# lightmeter_seeed1.net
KiCad netlist of a schematic drawn in EAGLE
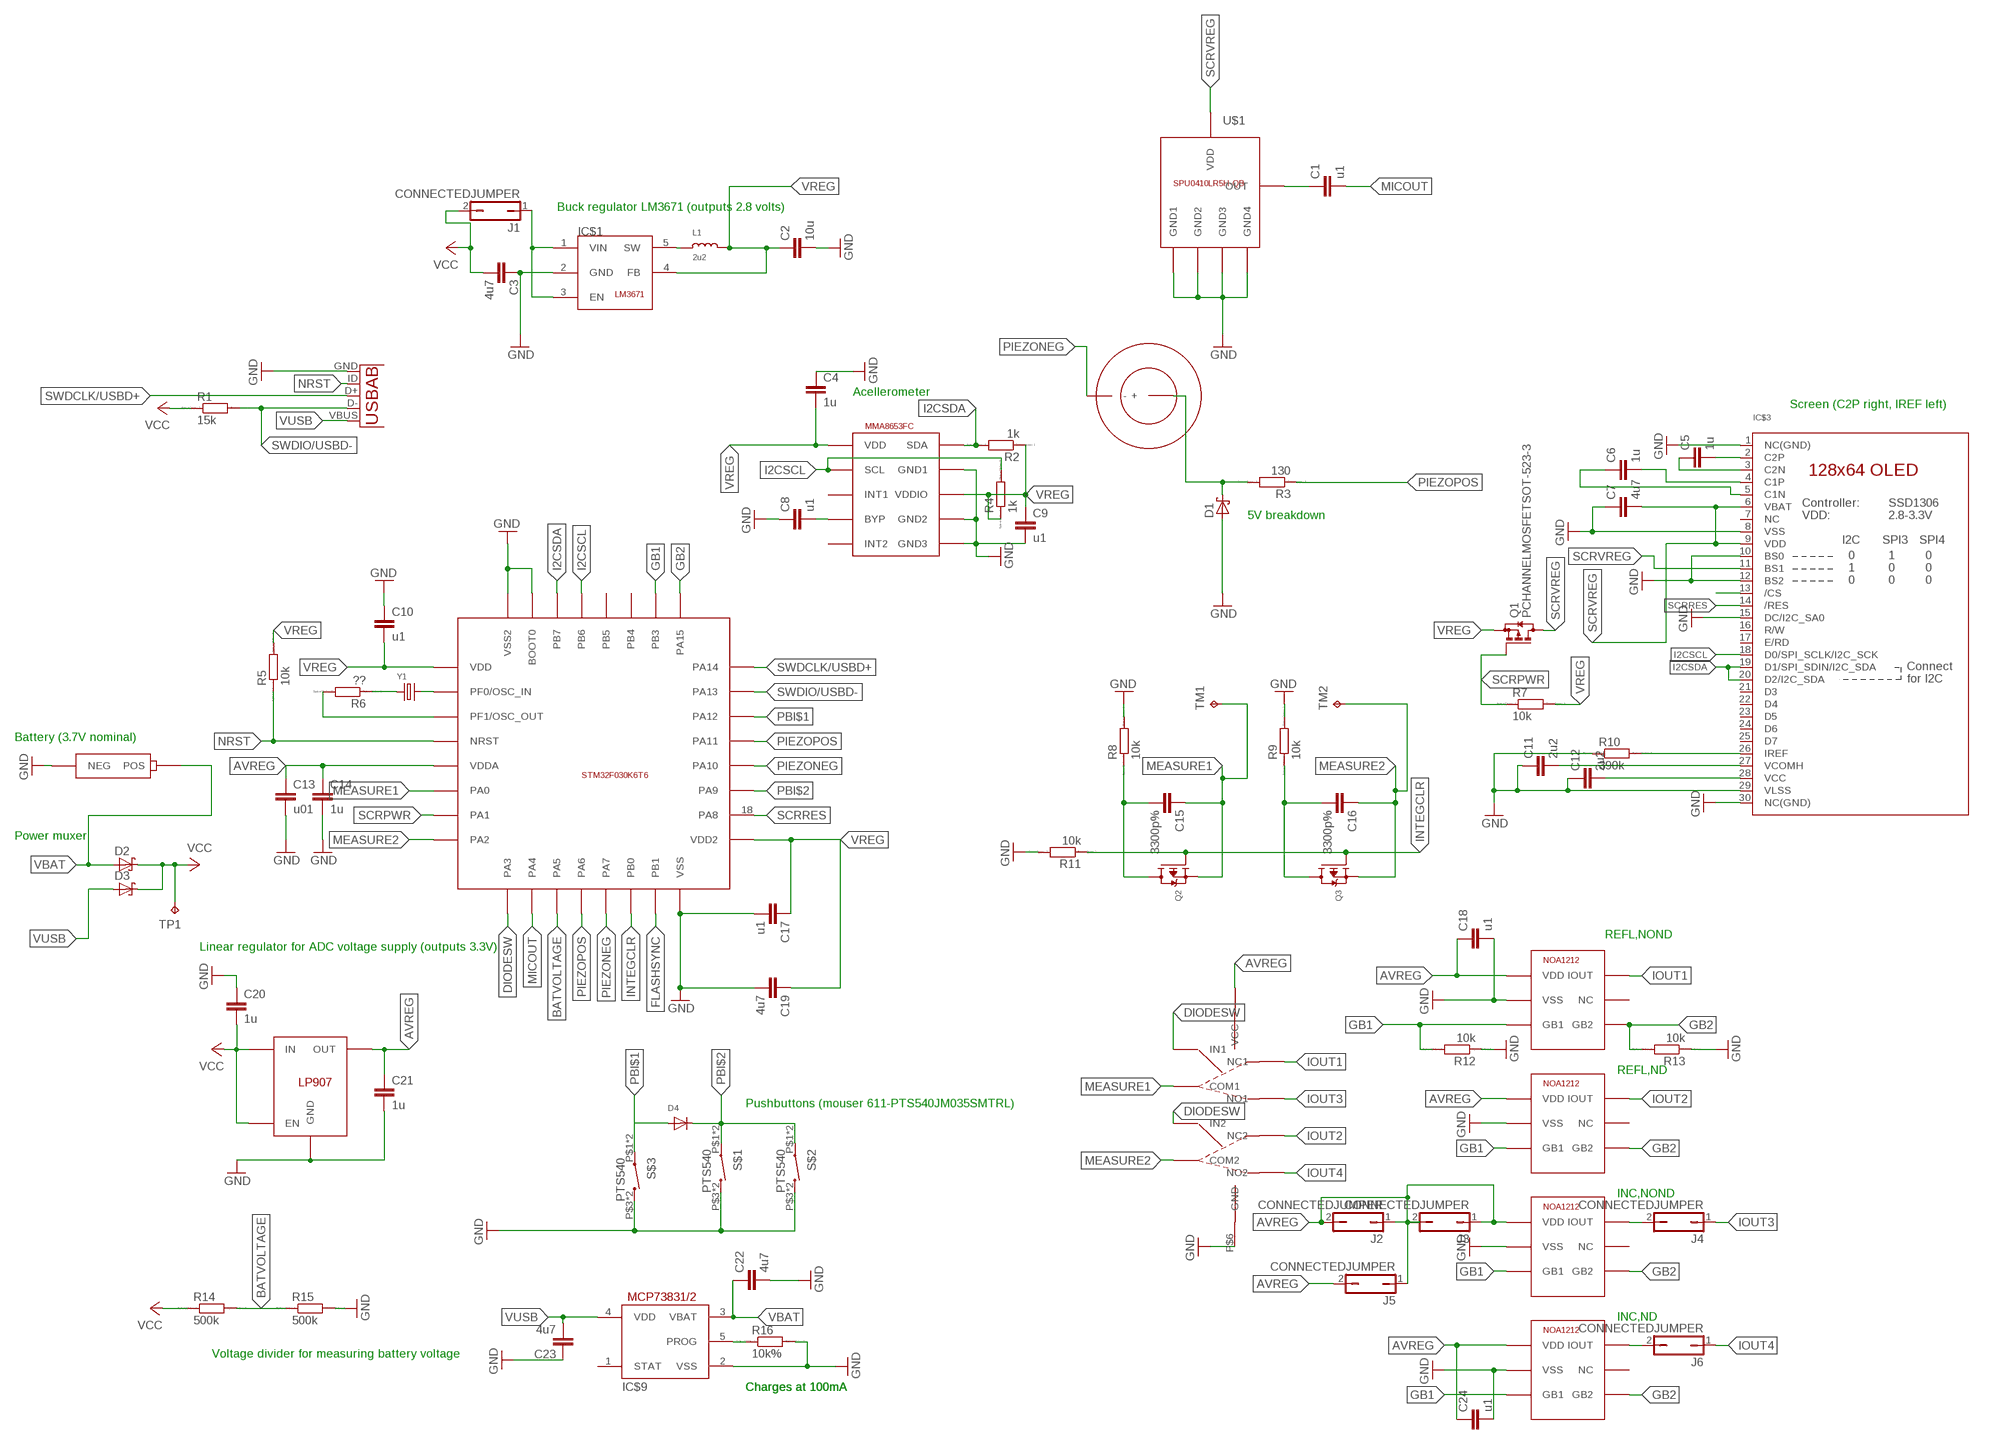
[diagram p0: schematic, sheet 1]

(export (version "E")
  (design (tool "Eeschema 10.0.6"))
  (components
    (comp (ref "C1")
      (value "u1")
      (footprint "eagle-import:C0402")
      (libsource (lib "eagle-import") (part "C-EUC0402"))
    )
    (comp (ref "C2")
      (value "10u")
      (footprint "eagle-import:C0402")
      (libsource (lib "eagle-import") (part "C-EUC0402"))
    )
    (comp (ref "C3")
      (value "4u7")
      (footprint "eagle-import:C0402")
      (libsource (lib "eagle-import") (part "C-EUC0402"))
    )
    (comp (ref "C4")
      (value "1u")
      (footprint "eagle-import:C0603")
      (libsource (lib "eagle-import") (part "C-EUC0603"))
    )
    (comp (ref "C5")
      (value "1u")
      (footprint "eagle-import:C0603")
      (libsource (lib "eagle-import") (part "C-EUC0603"))
    )
    (comp (ref "C6")
      (value "1u")
      (footprint "eagle-import:C0603")
      (libsource (lib "eagle-import") (part "C-EUC0603"))
    )
    (comp (ref "C7")
      (value "4u7")
      (footprint "eagle-import:C0402")
      (libsource (lib "eagle-import") (part "C-EUC0402"))
    )
    (comp (ref "C8")
      (value "u1")
      (footprint "eagle-import:C0603")
      (libsource (lib "eagle-import") (part "C-EUC0603"))
    )
    (comp (ref "C9")
      (value "u1")
      (footprint "eagle-import:C0402")
      (libsource (lib "eagle-import") (part "C-EUC0402"))
    )
    (comp (ref "C10")
      (value "u1")
      (footprint "eagle-import:C0402")
      (libsource (lib "eagle-import") (part "C-EUC0402"))
    )
    (comp (ref "C11")
      (value "2u2")
      (footprint "eagle-import:C0402")
      (libsource (lib "eagle-import") (part "C-EUC0402"))
    )
    (comp (ref "C12")
      (value "2u2")
      (footprint "eagle-import:C0402")
      (libsource (lib "eagle-import") (part "C-EUC0402"))
    )
    (comp (ref "C13")
      (value "u01")
      (footprint "eagle-import:GAP0402")
      (libsource (lib "eagle-import") (part "CGAP0402"))
    )
    (comp (ref "C14")
      (value "1u")
      (footprint "eagle-import:GAP0402")
      (libsource (lib "eagle-import") (part "CGAP0402"))
    )
    (comp (ref "C15")
      (value "3300p%")
      (footprint "eagle-import:C0603")
      (libsource (lib "eagle-import") (part "C-EUC0603"))
    )
    (comp (ref "C16")
      (value "3300p%")
      (footprint "eagle-import:C0603")
      (libsource (lib "eagle-import") (part "C-EUC0603"))
    )
    (comp (ref "C17")
      (value "u1")
      (footprint "eagle-import:C0402")
      (libsource (lib "eagle-import") (part "C-EUC0402"))
    )
    (comp (ref "C18")
      (value "u1")
      (footprint "eagle-import:C0402")
      (libsource (lib "eagle-import") (part "C-EUC0402"))
    )
    (comp (ref "C19")
      (value "4u7")
      (footprint "eagle-import:C0402")
      (libsource (lib "eagle-import") (part "C-EUC0402"))
    )
    (comp (ref "C20")
      (value "1u")
      (footprint "eagle-import:C0603")
      (libsource (lib "eagle-import") (part "C-EUC0603"))
    )
    (comp (ref "C21")
      (value "1u")
      (footprint "eagle-import:C0402")
      (libsource (lib "eagle-import") (part "C-EUC0402"))
    )
    (comp (ref "C22")
      (value "4u7")
      (footprint "eagle-import:C0402")
      (libsource (lib "eagle-import") (part "C-EUC0402"))
    )
    (comp (ref "C23")
      (value "4u7")
      (footprint "eagle-import:C0402")
      (libsource (lib "eagle-import") (part "C-EUC0402"))
    )
    (comp (ref "C24")
      (value "u1")
      (footprint "eagle-import:C0402")
      (libsource (lib "eagle-import") (part "C-EUC0402"))
    )
    (comp (ref "D1")
      (value "SCHOTTKY-DIODESOD-929")
      (footprint "eagle-import:SOD-923")
      (libsource (lib "eagle-import") (part "SCHOTTKY-DIODESOD-929"))
    )
    (comp (ref "D2")
      (value "SCHOTTKY-DIODEX3-DFN0603-2")
      (footprint "eagle-import:X3-DFN0603-2")
      (libsource (lib "eagle-import") (part "SCHOTTKY-DIODEX3-DFN0603-2"))
    )
    (comp (ref "D3")
      (value "SCHOTTKY-DIODEX3-DFN0603-2")
      (footprint "eagle-import:X3-DFN0603-2")
      (libsource (lib "eagle-import") (part "SCHOTTKY-DIODEX3-DFN0603-2"))
    )
    (comp (ref "D4")
      (value "DIODESOD-323F")
      (footprint "eagle-import:SOD-323F")
      (libsource (lib "eagle-import") (part "DIODESOD-323F"))
    )
    (comp (ref "IC$1")
      (value "LM3671")
      (footprint "eagle-import:SOT23-5")
      (libsource (lib "eagle-import") (part "LM3671"))
    )
    (comp (ref "IC$2")
      (value "MMA8653")
      (footprint "eagle-import:DFN-10")
      (libsource (lib "eagle-import") (part "MMA8653"))
    )
    (comp (ref "IC$3")
      (value "DISP_OLED_UG-2864HSWEG010.96\"")
      (footprint "eagle-import:UG-2864HSWEG01_0.96IN_WRAPAROUND")
      (libsource (lib "eagle-import") (part "DISP_OLED_UG-2864HSWEG010.96{dblquote}"))
    )
    (comp (ref "IC$4")
      (value "STM32F030K6T6")
      (footprint "eagle-import:QFP-32")
      (libsource (lib "eagle-import") (part "STM32F030K6T6"))
    )
    (comp (ref "IC$5")
      (value "NOA1212")
      (footprint "eagle-import:CUDFN6")
      (libsource (lib "eagle-import") (part "NOA1212"))
    )
    (comp (ref "IC$6")
      (value "LP5907")
      (footprint "eagle-import:SOT23-5L")
      (libsource (lib "eagle-import") (part "LP5907"))
    )
    (comp (ref "IC$7")
      (value "NOA1212")
      (footprint "eagle-import:CUDFN6")
      (libsource (lib "eagle-import") (part "NOA1212"))
    )
    (comp (ref "IC$8")
      (value "NOA1212")
      (footprint "eagle-import:CUDFN6")
      (libsource (lib "eagle-import") (part "NOA1212"))
    )
    (comp (ref "IC$9")
      (value "MCP73831/OT")
      (footprint "eagle-import:SOT23-5L")
      (libsource (lib "eagle-import") (part "MCP73831/OT"))
    )
    (comp (ref "IC$10")
      (value "NOA1212")
      (footprint "eagle-import:CUDFN6")
      (libsource (lib "eagle-import") (part "NOA1212"))
    )
    (comp (ref "J1")
      (value "CONNECTEDJUMPER")
      (footprint "eagle-import:JUMPER_R0402")
      (libsource (lib "eagle-import") (part "CONNECTEDJUMPER"))
    )
    (comp (ref "J2")
      (value "CONNECTEDJUMPER")
      (footprint "eagle-import:JUMPER_R0402")
      (libsource (lib "eagle-import") (part "CONNECTEDJUMPER"))
    )
    (comp (ref "J3")
      (value "CONNECTEDJUMPER")
      (footprint "eagle-import:JUMPER_R0402")
      (libsource (lib "eagle-import") (part "CONNECTEDJUMPER"))
    )
    (comp (ref "J4")
      (value "CONNECTEDJUMPER")
      (footprint "eagle-import:JUMPER_R0402")
      (libsource (lib "eagle-import") (part "CONNECTEDJUMPER"))
    )
    (comp (ref "J5")
      (value "CONNECTEDJUMPER")
      (footprint "eagle-import:JUMPER_R0402")
      (libsource (lib "eagle-import") (part "CONNECTEDJUMPER"))
    )
    (comp (ref "J6")
      (value "CONNECTEDJUMPER")
      (footprint "eagle-import:JUMPER_R0402")
      (libsource (lib "eagle-import") (part "CONNECTEDJUMPER"))
    )
    (comp (ref "L1")
      (value "2u2")
      (footprint "eagle-import:_0603")
      (libsource (lib "eagle-import") (part "INDUCTOR_0603"))
    )
    (comp (ref "Q1")
      (value "PCHANNELMOSFETSOT-523-3")
      (footprint "eagle-import:SOT-523-3")
      (libsource (lib "eagle-import") (part "PCHANNELMOSFETSOT-523-3"))
    )
    (comp (ref "Q2")
      (value "MOSFET-PWIDE")
      (footprint "eagle-import:SOT23-WIDE")
      (libsource (lib "eagle-import") (part "MOSFET-PWIDE"))
    )
    (comp (ref "Q3")
      (value "MOSFET-PWIDE")
      (footprint "eagle-import:SOT23-WIDE")
      (libsource (lib "eagle-import") (part "MOSFET-PWIDE"))
    )
    (comp (ref "R1")
      (value "15k")
      (footprint "eagle-import:R0402")
      (libsource (lib "eagle-import") (part "R-EU_R0402"))
    )
    (comp (ref "R2")
      (value "1k")
      (footprint "eagle-import:R0402")
      (libsource (lib "eagle-import") (part "R-EU_R0402"))
    )
    (comp (ref "R3")
      (value "130")
      (footprint "eagle-import:R0603")
      (libsource (lib "eagle-import") (part "R-EU_R0603"))
    )
    (comp (ref "R4")
      (value "1k")
      (footprint "eagle-import:R0402")
      (libsource (lib "eagle-import") (part "R-EU_R0402"))
    )
    (comp (ref "R5")
      (value "10k")
      (footprint "eagle-import:R0402")
      (libsource (lib "eagle-import") (part "R-EU_R0402"))
    )
    (comp (ref "R6")
      (value "??")
      (footprint "eagle-import:R0402")
      (libsource (lib "eagle-import") (part "R-EU_R0402"))
    )
    (comp (ref "R7")
      (value "10k")
      (footprint "eagle-import:R0402")
      (libsource (lib "eagle-import") (part "R-EU_R0402"))
    )
    (comp (ref "R8")
      (value "10k")
      (footprint "eagle-import:R0402")
      (libsource (lib "eagle-import") (part "R-EU_R0402"))
    )
    (comp (ref "R9")
      (value "10k")
      (footprint "eagle-import:R0402")
      (libsource (lib "eagle-import") (part "R-EU_R0402"))
    )
    (comp (ref "R10")
      (value "390k")
      (footprint "eagle-import:R0402")
      (libsource (lib "eagle-import") (part "R-EU_R0402"))
    )
    (comp (ref "R11")
      (value "10k")
      (footprint "eagle-import:R0402")
      (libsource (lib "eagle-import") (part "R-EU_R0402"))
    )
    (comp (ref "R12")
      (value "10k")
      (footprint "eagle-import:R0402")
      (libsource (lib "eagle-import") (part "R-EU_R0402"))
    )
    (comp (ref "R13")
      (value "10k")
      (footprint "eagle-import:R0402")
      (libsource (lib "eagle-import") (part "R-EU_R0402"))
    )
    (comp (ref "R14")
      (value "500k")
      (footprint "eagle-import:R0402")
      (libsource (lib "eagle-import") (part "R-EU_R0402"))
    )
    (comp (ref "R15")
      (value "500k")
      (footprint "eagle-import:R0402")
      (libsource (lib "eagle-import") (part "R-EU_R0402"))
    )
    (comp (ref "R16")
      (value "10k%")
      (footprint "eagle-import:R0402")
      (libsource (lib "eagle-import") (part "R-EU_R0402"))
    )
    (comp (ref "S$1")
      (value "PTS540")
      (footprint "eagle-import:PTS540BTM")
      (libsource (lib "eagle-import") (part "PTS540"))
    )
    (comp (ref "S$2")
      (value "PTS540")
      (footprint "eagle-import:PTS540BTM")
      (libsource (lib "eagle-import") (part "PTS540"))
    )
    (comp (ref "S$3")
      (value "PTS540")
      (footprint "eagle-import:PTS540BTM")
      (libsource (lib "eagle-import") (part "PTS540"))
    )
    (comp (ref "TM1")
      (value "TPB1,27")
      (footprint "eagle-import:B1,27")
      (libsource (lib "eagle-import") (part "TPB1,27"))
    )
    (comp (ref "TM2")
      (value "TPB1,27")
      (footprint "eagle-import:B1,27")
      (libsource (lib "eagle-import") (part "TPB1,27"))
    )
    (comp (ref "TP1")
      (value "TPB1,27")
      (footprint "eagle-import:B1,27")
      (libsource (lib "eagle-import") (part "TPB1,27"))
    )
    (comp (ref "U$1")
      (value "SPU0410LR5H-QBSPU0410LRSH-QB")
      (footprint "eagle-import:SPU0410LR5H-QB")
      (libsource (lib "eagle-import") (part "SPU0410LR5H-QBSPU0410LRSH-QB"))
    )
    (comp (ref "U$2")
      (value "PIEZOBENDER165")
      (footprint "eagle-import:PIEZOBENDER165")
      (libsource (lib "eagle-import") (part "PIEZOBENDER165"))
    )
    (comp (ref "U$3")
      (value "LIBAT")
      (footprint "eagle-import:78171-0002")
      (libsource (lib "eagle-import") (part "LIBAT"))
    )
    (comp (ref "U$4")
      (value "NLAS5223B")
      (footprint "eagle-import:WQFN10")
      (libsource (lib "eagle-import") (part "NLAS5223B"))
    )
    (comp (ref "U1")
      (value "USB-ABUSB-AB-MICRO-MIDMOUNT")
      (footprint "eagle-import:USB-AB-MICRO-MIDMOUNT")
      (libsource (lib "eagle-import") (part "USB-ABUSB-AB-MICRO-MIDMOUNT"))
    )
    (comp (ref "Y1")
      (value "CRYSTAL2.5X2.0MM")
      (footprint "eagle-import:CRYSTAL_2.5X2")
      (libsource (lib "eagle-import") (part "CRYSTAL2.5X2.0MM"))
    )
  )
  (nets
    (net (code "1") (name "AVREG") (class "Default")
      (node (ref "C13") (pin "1") (pinfunction "1_1") (pintype "passive"))
      (node (ref "C14") (pin "1") (pinfunction "1_1") (pintype "passive"))
      (node (ref "C18") (pin "1") (pinfunction "1_1") (pintype "passive"))
      (node (ref "C21") (pin "1") (pinfunction "1_1") (pintype "passive"))
      (node (ref "C24") (pin "1") (pinfunction "1_1") (pintype "passive"))
      (node (ref "IC$10") (pin "P$1") (pinfunction "VDD_P$1") (pintype "bidirectional"))
      (node (ref "IC$4") (pin "5") (pinfunction "VDDA_5") (pintype "bidirectional"))
      (node (ref "IC$5") (pin "P$1") (pinfunction "VDD_P$1") (pintype "bidirectional"))
      (node (ref "IC$6") (pin "5") (pinfunction "OUT_5") (pintype "bidirectional"))
      (node (ref "IC$7") (pin "P$1") (pinfunction "VDD_P$1") (pintype "bidirectional"))
      (node (ref "IC$8") (pin "P$1") (pinfunction "VDD_P$1") (pintype "bidirectional"))
      (node (ref "J2") (pin "1") (pinfunction "1_1") (pintype "passive"))
      (node (ref "J2") (pin "2") (pinfunction "2_2") (pintype "passive"))
      (node (ref "J3") (pin "1") (pinfunction "1_1") (pintype "passive"))
      (node (ref "J3") (pin "2") (pinfunction "2_2") (pintype "passive"))
      (node (ref "J5") (pin "1") (pinfunction "1_1") (pintype "passive"))
      (node (ref "J5") (pin "2") (pinfunction "2_2") (pintype "passive"))
      (node (ref "U$4") (pin "P$1") (pinfunction "VCC_P$1") (pintype "bidirectional"))
    )
    (net (code "2") (name "BATVOLTAGE") (class "Default")
      (node (ref "IC$4") (pin "11") (pinfunction "PA5_11") (pintype "bidirectional"))
      (node (ref "R14") (pin "2") (pinfunction "2_2") (pintype "passive"))
      (node (ref "R15") (pin "1") (pinfunction "1_1") (pintype "passive"))
    )
    (net (code "3") (name "DIODESW") (class "Default")
      (node (ref "IC$4") (pin "9") (pinfunction "PA3_9") (pintype "bidirectional"))
      (node (ref "U$4") (pin "P$4") (pinfunction "IN1_P$4") (pintype "bidirectional"))
      (node (ref "U$4") (pin "P$8") (pinfunction "IN2_P$8") (pintype "bidirectional"))
    )
    (net (code "4") (name "FLASHSYNC") (class "Default")
      (node (ref "IC$4") (pin "15") (pinfunction "PB1_15") (pintype "bidirectional"))
    )
    (net (code "5") (name "GB1") (class "Default")
      (node (ref "IC$10") (pin "P$3") (pinfunction "GB1_P$3") (pintype "bidirectional"))
      (node (ref "IC$4") (pin "26") (pinfunction "PB3_26") (pintype "bidirectional"))
      (node (ref "IC$5") (pin "P$3") (pinfunction "GB1_P$3") (pintype "bidirectional"))
      (node (ref "IC$7") (pin "P$3") (pinfunction "GB1_P$3") (pintype "bidirectional"))
      (node (ref "IC$8") (pin "P$3") (pinfunction "GB1_P$3") (pintype "bidirectional"))
      (node (ref "R12") (pin "2") (pinfunction "2_2") (pintype "passive"))
    )
    (net (code "6") (name "GB2") (class "Default")
      (node (ref "IC$10") (pin "P$4") (pinfunction "GB2_P$4") (pintype "bidirectional"))
      (node (ref "IC$4") (pin "25") (pinfunction "PA15_25") (pintype "bidirectional"))
      (node (ref "IC$5") (pin "P$4") (pinfunction "GB2_P$4") (pintype "bidirectional"))
      (node (ref "IC$7") (pin "P$4") (pinfunction "GB2_P$4") (pintype "bidirectional"))
      (node (ref "IC$8") (pin "P$4") (pinfunction "GB2_P$4") (pintype "bidirectional"))
      (node (ref "R13") (pin "2") (pinfunction "2_2") (pintype "passive"))
    )
    (net (code "7") (name "GND") (class "Default")
      (node (ref "C10") (pin "1") (pinfunction "1_1") (pintype "passive"))
      (node (ref "C11") (pin "1") (pinfunction "1_1") (pintype "passive"))
      (node (ref "C12") (pin "1") (pinfunction "1_1") (pintype "passive"))
      (node (ref "C13") (pin "2") (pinfunction "2_2") (pintype "passive"))
      (node (ref "C14") (pin "2") (pinfunction "2_2") (pintype "passive"))
      (node (ref "C17") (pin "2") (pinfunction "2_2") (pintype "passive"))
      (node (ref "C18") (pin "2") (pinfunction "2_2") (pintype "passive"))
      (node (ref "C19") (pin "2") (pinfunction "2_2") (pintype "passive"))
      (node (ref "C2") (pin "2") (pinfunction "2_2") (pintype "passive"))
      (node (ref "C20") (pin "1") (pinfunction "1_1") (pintype "passive"))
      (node (ref "C21") (pin "2") (pinfunction "2_2") (pintype "passive"))
      (node (ref "C22") (pin "2") (pinfunction "2_2") (pintype "passive"))
      (node (ref "C23") (pin "1") (pinfunction "1_1") (pintype "passive"))
      (node (ref "C24") (pin "2") (pinfunction "2_2") (pintype "passive"))
      (node (ref "C3") (pin "1") (pinfunction "1_1") (pintype "passive"))
      (node (ref "C4") (pin "1") (pinfunction "1_1") (pintype "passive"))
      (node (ref "C7") (pin "1") (pinfunction "1_1") (pintype "passive"))
      (node (ref "C8") (pin "1") (pinfunction "1_1") (pintype "passive"))
      (node (ref "C9") (pin "2") (pinfunction "2_2") (pintype "passive"))
      (node (ref "D1") (pin "P$1") (pinfunction "A_P$1") (pintype "passive"))
      (node (ref "IC$1") (pin "2") (pinfunction "GND_2") (pintype "bidirectional"))
      (node (ref "IC$10") (pin "P$2") (pinfunction "VSS_P$2") (pintype "bidirectional"))
      (node (ref "IC$10") (pin "P$7") (pinfunction "VSS_P$7") (pintype "bidirectional"))
      (node (ref "IC$2") (pin "P$6") (pinfunction "GND3_P$6") (pintype "bidirectional"))
      (node (ref "IC$2") (pin "P$7") (pinfunction "GND2_P$7") (pintype "bidirectional"))
      (node (ref "IC$2") (pin "P$9") (pinfunction "GND1_P$9") (pintype "bidirectional"))
      (node (ref "IC$3") (pin "1") (pinfunction "NC(GND)_1") (pintype "input"))
      (node (ref "IC$3") (pin "10") (pinfunction "BS0_10") (pintype "input"))
      (node (ref "IC$3") (pin "12") (pinfunction "BS2_12") (pintype "input"))
      (node (ref "IC$3") (pin "15") (pinfunction "DC/I2C_SA0_15") (pintype "input"))
      (node (ref "IC$3") (pin "29") (pinfunction "VLSS_29") (pintype "power_in"))
      (node (ref "IC$3") (pin "30") (pinfunction "NC(GND)_30") (pintype "input"))
      (node (ref "IC$3") (pin "8") (pinfunction "VSS_8") (pintype "power_in"))
      (node (ref "IC$4") (pin "16") (pinfunction "VSS_16") (pintype "bidirectional"))
      (node (ref "IC$4") (pin "31") (pinfunction "BOOT0_31") (pintype "bidirectional"))
      (node (ref "IC$4") (pin "32") (pinfunction "VSS2_32") (pintype "bidirectional"))
      (node (ref "IC$5") (pin "P$2") (pinfunction "VSS_P$2") (pintype "bidirectional"))
      (node (ref "IC$5") (pin "P$7") (pinfunction "VSS_P$7") (pintype "bidirectional"))
      (node (ref "IC$6") (pin "2") (pinfunction "GND_2") (pintype "bidirectional"))
      (node (ref "IC$7") (pin "P$2") (pinfunction "VSS_P$2") (pintype "bidirectional"))
      (node (ref "IC$7") (pin "P$7") (pinfunction "VSS_P$7") (pintype "bidirectional"))
      (node (ref "IC$8") (pin "P$2") (pinfunction "VSS_P$2") (pintype "bidirectional"))
      (node (ref "IC$8") (pin "P$7") (pinfunction "VSS_P$7") (pintype "bidirectional"))
      (node (ref "IC$9") (pin "2") (pinfunction "VSS_2") (pintype "power_in"))
      (node (ref "R10") (pin "1") (pinfunction "1_1") (pintype "passive"))
      (node (ref "R11") (pin "2") (pinfunction "2_2") (pintype "passive"))
      (node (ref "R12") (pin "1") (pinfunction "1_1") (pintype "passive"))
      (node (ref "R13") (pin "1") (pinfunction "1_1") (pintype "passive"))
      (node (ref "R15") (pin "2") (pinfunction "2_2") (pintype "passive"))
      (node (ref "R16") (pin "2") (pinfunction "2_2") (pintype "passive"))
      (node (ref "R8") (pin "2") (pinfunction "2_2") (pintype "passive"))
      (node (ref "R9") (pin "2") (pinfunction "2_2") (pintype "passive"))
      (node (ref "S$1") (pin "P$3") (pinfunction "2_P$3") (pintype "passive"))
      (node (ref "S$1") (pin "P$4") (pinfunction "2_P$4") (pintype "passive"))
      (node (ref "S$2") (pin "P$3") (pinfunction "2_P$3") (pintype "passive"))
      (node (ref "S$2") (pin "P$4") (pinfunction "2_P$4") (pintype "passive"))
      (node (ref "S$3") (pin "P$3") (pinfunction "2_P$3") (pintype "passive"))
      (node (ref "S$3") (pin "P$4") (pinfunction "2_P$4") (pintype "passive"))
      (node (ref "U$1") (pin "P$2") (pinfunction "GND1_P$2") (pintype "bidirectional"))
      (node (ref "U$1") (pin "P$3") (pinfunction "GND2_P$3") (pintype "bidirectional"))
      (node (ref "U$1") (pin "P$5") (pinfunction "GND3_P$5") (pintype "bidirectional"))
      (node (ref "U$1") (pin "P$6") (pinfunction "GND4_P$6") (pintype "bidirectional"))
      (node (ref "U$3") (pin "P$1") (pinfunction "NEG_P$1") (pintype "bidirectional"))
      (node (ref "U$4") (pin "P$6") (pinfunction "GND_P$6") (pintype "bidirectional"))
      (node (ref "U1") (pin "GND") (pinfunction "GND_GND") (pintype "bidirectional"))
    )
    (net (code "8") (name "I2CSCL") (class "Default")
      (node (ref "IC$2") (pin "P$2") (pinfunction "SCL_P$2") (pintype "bidirectional"))
      (node (ref "IC$3") (pin "18") (pinfunction "D0/SPI_SCLK/I2C_SCK_18") (pintype "bidirectional"))
      (node (ref "IC$4") (pin "29") (pinfunction "PB6_29") (pintype "bidirectional"))
      (node (ref "R4") (pin "2") (pinfunction "2_2") (pintype "passive"))
    )
    (net (code "9") (name "I2CSDA") (class "Default")
      (node (ref "IC$2") (pin "P$10") (pinfunction "SDA_P$10") (pintype "bidirectional"))
      (node (ref "IC$3") (pin "19") (pinfunction "D1/SPI_SDIN/I2C_SDA_19") (pintype "bidirectional"))
      (node (ref "IC$3") (pin "20") (pinfunction "D2/I2C_SDA_20") (pintype "bidirectional"))
      (node (ref "IC$4") (pin "30") (pinfunction "PB7_30") (pintype "bidirectional"))
      (node (ref "R2") (pin "2") (pinfunction "2_2") (pintype "passive"))
    )
    (net (code "10") (name "INTEGCLR") (class "Default")
      (node (ref "IC$4") (pin "14") (pinfunction "PB0_14") (pintype "bidirectional"))
      (node (ref "Q2") (pin "1") (pinfunction "G_1") (pintype "passive"))
      (node (ref "Q3") (pin "1") (pinfunction "G_1") (pintype "passive"))
      (node (ref "R11") (pin "1") (pinfunction "1_1") (pintype "passive"))
    )
    (net (code "11") (name "IOUT1") (class "Default")
      (node (ref "IC$5") (pin "P$6") (pinfunction "IOUT_P$6") (pintype "bidirectional"))
      (node (ref "U$4") (pin "P$5") (pinfunction "NC1_P$5") (pintype "bidirectional"))
    )
    (net (code "12") (name "IOUT2") (class "Default")
      (node (ref "IC$7") (pin "P$6") (pinfunction "IOUT_P$6") (pintype "bidirectional"))
      (node (ref "U$4") (pin "P$7") (pinfunction "NC2_P$7") (pintype "bidirectional"))
    )
    (net (code "13") (name "IOUT3") (class "Default")
      (node (ref "J4") (pin "1") (pinfunction "1_1") (pintype "passive"))
      (node (ref "U$4") (pin "P$2") (pinfunction "NO1_P$2") (pintype "bidirectional"))
    )
    (net (code "14") (name "IOUT4") (class "Default")
      (node (ref "J6") (pin "1") (pinfunction "1_1") (pintype "passive"))
      (node (ref "U$4") (pin "P$10") (pinfunction "NO2_P$10") (pintype "bidirectional"))
    )
    (net (code "15") (name "MEASURE1") (class "Default")
      (node (ref "C15") (pin "1") (pinfunction "1_1") (pintype "passive"))
      (node (ref "IC$4") (pin "6") (pinfunction "PA0_6") (pintype "bidirectional"))
      (node (ref "Q2") (pin "2") (pinfunction "S_2") (pintype "passive"))
      (node (ref "TM1") (pin "TP") (pinfunction "TP_TP") (pintype "input"))
      (node (ref "U$4") (pin "P$3") (pinfunction "COM1_P$3") (pintype "bidirectional"))
    )
    (net (code "16") (name "MEASURE2") (class "Default")
      (node (ref "C16") (pin "1") (pinfunction "1_1") (pintype "passive"))
      (node (ref "IC$4") (pin "8") (pinfunction "PA2_8") (pintype "bidirectional"))
      (node (ref "Q3") (pin "2") (pinfunction "S_2") (pintype "passive"))
      (node (ref "TM2") (pin "TP") (pinfunction "TP_TP") (pintype "input"))
      (node (ref "U$4") (pin "P$9") (pinfunction "COM2_P$9") (pintype "bidirectional"))
    )
    (net (code "17") (name "MICOUT") (class "Default")
      (node (ref "C1") (pin "2") (pinfunction "2_2") (pintype "passive"))
      (node (ref "IC$4") (pin "10") (pinfunction "PA4_10") (pintype "bidirectional"))
    )
    (net (code "18") (name "NRST") (class "Default")
      (node (ref "IC$4") (pin "4") (pinfunction "NRST_4") (pintype "bidirectional"))
      (node (ref "R5") (pin "1") (pinfunction "1_1") (pintype "passive"))
      (node (ref "U1") (pin "ID") (pinfunction "USBID_ID") (pintype "bidirectional"))
    )
    (net (code "19") (name "Net-(D1-C)") (class "Default")
      (node (ref "D1") (pin "P$2") (pinfunction "C_P$2") (pintype "passive"))
      (node (ref "R3") (pin "2") (pinfunction "2_2") (pintype "passive"))
      (node (ref "U$2") (pin "P$2") (pinfunction "+_P$2") (pintype "bidirectional"))
    )
    (net (code "20") (name "Net-(IC$1-EN)") (class "Default")
      (node (ref "IC$1") (pin "1") (pinfunction "VIN_1") (pintype "bidirectional"))
      (node (ref "IC$1") (pin "3") (pinfunction "EN_3") (pintype "bidirectional"))
      (node (ref "J1") (pin "1") (pinfunction "1_1") (pintype "passive"))
    )
    (net (code "21") (name "Net-(IC$1-SW)") (class "Default")
      (node (ref "IC$1") (pin "5") (pinfunction "SW_5") (pintype "bidirectional"))
      (node (ref "L1") (pin "1") (pinfunction "1_1") (pintype "passive"))
    )
    (net (code "22") (name "Net-(IC$2-BYP)") (class "Default")
      (node (ref "C8") (pin "2") (pinfunction "2_2") (pintype "passive"))
      (node (ref "IC$2") (pin "P$4") (pinfunction "BYP_P$4") (pintype "bidirectional"))
    )
    (net (code "23") (name "Net-(IC$3-C1N)") (class "Default")
      (node (ref "C6") (pin "1") (pinfunction "1_1") (pintype "passive"))
      (node (ref "IC$3") (pin "5") (pinfunction "C1N_5") (pintype "input"))
    )
    (net (code "24") (name "Net-(IC$3-C1P)") (class "Default")
      (node (ref "C6") (pin "2") (pinfunction "2_2") (pintype "passive"))
      (node (ref "IC$3") (pin "4") (pinfunction "C1P_4") (pintype "input"))
    )
    (net (code "25") (name "Net-(IC$3-C2N)") (class "Default")
      (node (ref "C5") (pin "1") (pinfunction "1_1") (pintype "passive"))
      (node (ref "IC$3") (pin "3") (pinfunction "C2N_3") (pintype "input"))
    )
    (net (code "26") (name "Net-(IC$3-C2P)") (class "Default")
      (node (ref "C5") (pin "2") (pinfunction "2_2") (pintype "passive"))
      (node (ref "IC$3") (pin "2") (pinfunction "C2P_2") (pintype "input"))
    )
    (net (code "27") (name "Net-(IC$3-IREF)") (class "Default")
      (node (ref "IC$3") (pin "26") (pinfunction "IREF_26") (pintype "input"))
      (node (ref "R10") (pin "2") (pinfunction "2_2") (pintype "passive"))
    )
    (net (code "28") (name "Net-(IC$3-VCC)") (class "Default")
      (node (ref "C12") (pin "2") (pinfunction "2_2") (pintype "passive"))
      (node (ref "IC$3") (pin "28") (pinfunction "VCC_28") (pintype "power_in"))
    )
    (net (code "29") (name "Net-(IC$3-VCOMH)") (class "Default")
      (node (ref "C11") (pin "2") (pinfunction "2_2") (pintype "passive"))
      (node (ref "IC$3") (pin "27") (pinfunction "VCOMH_27") (pintype "output"))
    )
    (net (code "30") (name "Net-(IC$4-PF0{slash}OSC_IN)") (class "Default")
      (node (ref "IC$4") (pin "2") (pinfunction "PF0/OSC_IN_2") (pintype "bidirectional"))
      (node (ref "Y1") (pin "3") (pinfunction "2_3") (pintype "passive"))
    )
    (net (code "31") (name "Net-(IC$4-PF1{slash}OSC_OUT)") (class "Default")
      (node (ref "IC$4") (pin "3") (pinfunction "PF1/OSC_OUT_3") (pintype "bidirectional"))
      (node (ref "R6") (pin "2") (pinfunction "2_2") (pintype "passive"))
    )
    (net (code "32") (name "Net-(IC$8-IOUT)") (class "Default")
      (node (ref "IC$8") (pin "P$6") (pinfunction "IOUT_P$6") (pintype "bidirectional"))
      (node (ref "J4") (pin "2") (pinfunction "2_2") (pintype "passive"))
    )
    (net (code "33") (name "Net-(IC$9-PROG)") (class "Default")
      (node (ref "IC$9") (pin "5") (pinfunction "PROG_5") (pintype "input"))
      (node (ref "R16") (pin "1") (pinfunction "1_1") (pintype "passive"))
    )
    (net (code "34") (name "Net-(IC$10-IOUT)") (class "Default")
      (node (ref "IC$10") (pin "P$6") (pinfunction "IOUT_P$6") (pintype "bidirectional"))
      (node (ref "J6") (pin "2") (pinfunction "2_2") (pintype "passive"))
    )
    (net (code "35") (name "Net-(Q2-D)") (class "Default")
      (node (ref "C15") (pin "2") (pinfunction "2_2") (pintype "passive"))
      (node (ref "Q2") (pin "3") (pinfunction "D_3") (pintype "passive"))
      (node (ref "R8") (pin "1") (pinfunction "1_1") (pintype "passive"))
    )
    (net (code "36") (name "Net-(Q3-D)") (class "Default")
      (node (ref "C16") (pin "2") (pinfunction "2_2") (pintype "passive"))
      (node (ref "Q3") (pin "3") (pinfunction "D_3") (pintype "passive"))
      (node (ref "R9") (pin "1") (pinfunction "1_1") (pintype "passive"))
    )
    (net (code "37") (name "Net-(R6-Pad1)") (class "Default")
      (node (ref "R6") (pin "1") (pinfunction "1_1") (pintype "passive"))
      (node (ref "Y1") (pin "1") (pinfunction "1_1") (pintype "passive"))
    )
    (net (code "38") (name "Net-(U$1-OUT)") (class "Default")
      (node (ref "C1") (pin "1") (pinfunction "1_1") (pintype "passive"))
      (node (ref "U$1") (pin "P$1") (pinfunction "OUT_P$1") (pintype "bidirectional"))
    )
    (net (code "39") (name "PBI$1") (class "Default")
      (node (ref "D4") (pin "A") (pinfunction "A_A") (pintype "passive"))
      (node (ref "IC$4") (pin "22") (pinfunction "PA12_22") (pintype "bidirectional"))
      (node (ref "S$3") (pin "P$1") (pinfunction "1_P$1") (pintype "passive"))
      (node (ref "S$3") (pin "P$2") (pinfunction "1_P$2") (pintype "passive"))
    )
    (net (code "40") (name "PBI$2") (class "Default")
      (node (ref "D4") (pin "C") (pinfunction "C_C") (pintype "passive"))
      (node (ref "IC$4") (pin "19") (pinfunction "PA9_19") (pintype "bidirectional"))
      (node (ref "S$1") (pin "P$1") (pinfunction "1_P$1") (pintype "passive"))
      (node (ref "S$1") (pin "P$2") (pinfunction "1_P$2") (pintype "passive"))
      (node (ref "S$2") (pin "P$1") (pinfunction "1_P$1") (pintype "passive"))
      (node (ref "S$2") (pin "P$2") (pinfunction "1_P$2") (pintype "passive"))
    )
    (net (code "41") (name "PIEZONEG") (class "Default")
      (node (ref "IC$4") (pin "13") (pinfunction "PA7_13") (pintype "bidirectional"))
      (node (ref "IC$4") (pin "20") (pinfunction "PA10_20") (pintype "bidirectional"))
      (node (ref "U$2") (pin "P$1") (pinfunction "-_P$1") (pintype "bidirectional"))
    )
    (net (code "42") (name "PIEZOPOS") (class "Default")
      (node (ref "IC$4") (pin "12") (pinfunction "PA6_12") (pintype "bidirectional"))
      (node (ref "IC$4") (pin "21") (pinfunction "PA11_21") (pintype "bidirectional"))
      (node (ref "R3") (pin "1") (pinfunction "1_1") (pintype "passive"))
    )
    (net (code "43") (name "SCRPWR") (class "Default")
      (node (ref "IC$4") (pin "7") (pinfunction "PA1_7") (pintype "bidirectional"))
      (node (ref "Q1") (pin "P$2") (pinfunction "G_P$2") (pintype "passive"))
      (node (ref "R7") (pin "1") (pinfunction "1_1") (pintype "passive"))
    )
    (net (code "44") (name "SCRRES") (class "Default")
      (node (ref "IC$3") (pin "14") (pinfunction "/RES_14") (pintype "input"))
      (node (ref "IC$4") (pin "18") (pinfunction "PA8_18") (pintype "bidirectional"))
    )
    (net (code "45") (name "SCRVREG") (class "Default")
      (node (ref "C7") (pin "2") (pinfunction "2_2") (pintype "passive"))
      (node (ref "IC$3") (pin "11") (pinfunction "BS1_11") (pintype "input"))
      (node (ref "IC$3") (pin "6") (pinfunction "VBAT_6") (pintype "input"))
      (node (ref "IC$3") (pin "9") (pinfunction "VDD_9") (pintype "power_in"))
      (node (ref "Q1") (pin "P$1") (pinfunction "D_P$1") (pintype "passive"))
      (node (ref "U$1") (pin "P$4") (pinfunction "VDD_P$4") (pintype "bidirectional"))
    )
    (net (code "46") (name "SWDCLK{slash}USBD+") (class "Default")
      (node (ref "IC$4") (pin "24") (pinfunction "PA14_24") (pintype "bidirectional"))
      (node (ref "U1") (pin "D+") (pinfunction "D+_D+") (pintype "bidirectional"))
    )
    (net (code "47") (name "SWDIO{slash}USBD-") (class "Default")
      (node (ref "IC$4") (pin "23") (pinfunction "PA13_23") (pintype "bidirectional"))
      (node (ref "R1") (pin "2") (pinfunction "2_2") (pintype "passive"))
      (node (ref "U1") (pin "D-") (pinfunction "D-_D-") (pintype "bidirectional"))
    )
    (net (code "48") (name "VBAT") (class "Default")
      (node (ref "C22") (pin "1") (pinfunction "1_1") (pintype "passive"))
      (node (ref "D2") (pin "P$1") (pinfunction "A_P$1") (pintype "passive"))
      (node (ref "IC$9") (pin "3") (pinfunction "VBAT_3") (pintype "bidirectional"))
      (node (ref "U$3") (pin "P$2") (pinfunction "POS_P$2") (pintype "bidirectional"))
    )
    (net (code "49") (name "VCC") (class "Default")
      (node (ref "C20") (pin "2") (pinfunction "2_2") (pintype "passive"))
      (node (ref "C3") (pin "2") (pinfunction "2_2") (pintype "passive"))
      (node (ref "D2") (pin "P$2") (pinfunction "C_P$2") (pintype "passive"))
      (node (ref "D3") (pin "P$2") (pinfunction "C_P$2") (pintype "passive"))
      (node (ref "IC$6") (pin "1") (pinfunction "IN_1") (pintype "bidirectional"))
      (node (ref "IC$6") (pin "3") (pinfunction "EN_3") (pintype "bidirectional"))
      (node (ref "J1") (pin "2") (pinfunction "2_2") (pintype "passive"))
      (node (ref "R1") (pin "1") (pinfunction "1_1") (pintype "passive"))
      (node (ref "R14") (pin "1") (pinfunction "1_1") (pintype "passive"))
      (node (ref "TP1") (pin "TP") (pinfunction "TP_TP") (pintype "input"))
    )
    (net (code "50") (name "VREG") (class "Default")
      (node (ref "C10") (pin "2") (pinfunction "2_2") (pintype "passive"))
      (node (ref "C17") (pin "1") (pinfunction "1_1") (pintype "passive"))
      (node (ref "C19") (pin "1") (pinfunction "1_1") (pintype "passive"))
      (node (ref "C2") (pin "1") (pinfunction "1_1") (pintype "passive"))
      (node (ref "C4") (pin "2") (pinfunction "2_2") (pintype "passive"))
      (node (ref "C9") (pin "1") (pinfunction "1_1") (pintype "passive"))
      (node (ref "IC$1") (pin "4") (pinfunction "FB_4") (pintype "bidirectional"))
      (node (ref "IC$2") (pin "P$1") (pinfunction "VDD_P$1") (pintype "bidirectional"))
      (node (ref "IC$2") (pin "P$8") (pinfunction "VDDIO_P$8") (pintype "bidirectional"))
      (node (ref "IC$4") (pin "1") (pinfunction "VDD_1") (pintype "bidirectional"))
      (node (ref "IC$4") (pin "17") (pinfunction "VDD2_17") (pintype "bidirectional"))
      (node (ref "L1") (pin "2") (pinfunction "2_2") (pintype "passive"))
      (node (ref "Q1") (pin "P$3") (pinfunction "S_P$3") (pintype "passive"))
      (node (ref "R2") (pin "1") (pinfunction "1_1") (pintype "passive"))
      (node (ref "R4") (pin "1") (pinfunction "1_1") (pintype "passive"))
      (node (ref "R5") (pin "2") (pinfunction "2_2") (pintype "passive"))
      (node (ref "R7") (pin "2") (pinfunction "2_2") (pintype "passive"))
    )
    (net (code "51") (name "VUSB") (class "Default")
      (node (ref "C23") (pin "2") (pinfunction "2_2") (pintype "passive"))
      (node (ref "D3") (pin "P$1") (pinfunction "A_P$1") (pintype "passive"))
      (node (ref "IC$9") (pin "4") (pinfunction "VDD_4") (pintype "power_in"))
      (node (ref "U1") (pin "VBUS") (pinfunction "VBUS_VBUS") (pintype "bidirectional"))
    )
    (net (code "52") (name "unconnected-(IC$2-INT1-PadP$3)") (class "Default")
      (node (ref "IC$2") (pin "P$3") (pinfunction "INT1_P$3") (pintype "bidirectional"))
    )
    (net (code "53") (name "unconnected-(IC$2-INT2-PadP$5)") (class "Default")
      (node (ref "IC$2") (pin "P$5") (pinfunction "INT2_P$5") (pintype "bidirectional"))
    )
    (net (code "54") (name "unconnected-(IC$3-D3-Pad21)") (class "Default")
      (node (ref "IC$3") (pin "21") (pinfunction "D3_21") (pintype "bidirectional"))
    )
    (net (code "55") (name "unconnected-(IC$3-D4-Pad22)") (class "Default")
      (node (ref "IC$3") (pin "22") (pinfunction "D4_22") (pintype "bidirectional"))
    )
    (net (code "56") (name "unconnected-(IC$3-D5-Pad23)") (class "Default")
      (node (ref "IC$3") (pin "23") (pinfunction "D5_23") (pintype "bidirectional"))
    )
    (net (code "57") (name "unconnected-(IC$3-D6-Pad24)") (class "Default")
      (node (ref "IC$3") (pin "24") (pinfunction "D6_24") (pintype "bidirectional"))
    )
    (net (code "58") (name "unconnected-(IC$3-D7-Pad25)") (class "Default")
      (node (ref "IC$3") (pin "25") (pinfunction "D7_25") (pintype "bidirectional"))
    )
    (net (code "59") (name "unconnected-(IC$3-E{slash}RD-Pad17)") (class "Default")
      (node (ref "IC$3") (pin "17") (pinfunction "E/RD_17") (pintype "input"))
    )
    (net (code "60") (name "unconnected-(IC$3-NC-Pad7)") (class "Default")
      (node (ref "IC$3") (pin "7") (pinfunction "NC_7") (pintype "no_connect"))
    )
    (net (code "61") (name "unconnected-(IC$3-R{slash}W-Pad16)") (class "Default")
      (node (ref "IC$3") (pin "16") (pinfunction "R/W_16") (pintype "input"))
    )
    (net (code "62") (name "unconnected-(IC$3-{slash}CS-Pad13)") (class "Default")
      (node (ref "IC$3") (pin "13") (pinfunction "/CS_13") (pintype "input"))
    )
    (net (code "63") (name "unconnected-(IC$4-PB4-Pad27)") (class "Default")
      (node (ref "IC$4") (pin "27") (pinfunction "PB4_27") (pintype "bidirectional"))
    )
    (net (code "64") (name "unconnected-(IC$4-PB5-Pad28)") (class "Default")
      (node (ref "IC$4") (pin "28") (pinfunction "PB5_28") (pintype "bidirectional"))
    )
    (net (code "65") (name "unconnected-(IC$5-NC-PadP$5)") (class "Default")
      (node (ref "IC$5") (pin "P$5") (pinfunction "NC_P$5") (pintype "bidirectional"))
    )
    (net (code "66") (name "unconnected-(IC$7-NC-PadP$5)") (class "Default")
      (node (ref "IC$7") (pin "P$5") (pinfunction "NC_P$5") (pintype "bidirectional"))
    )
    (net (code "67") (name "unconnected-(IC$8-NC-PadP$5)") (class "Default")
      (node (ref "IC$8") (pin "P$5") (pinfunction "NC_P$5") (pintype "bidirectional"))
    )
    (net (code "68") (name "unconnected-(IC$9-STAT-Pad1)") (class "Default")
      (node (ref "IC$9") (pin "1") (pinfunction "STAT_1") (pintype "output"))
    )
    (net (code "69") (name "unconnected-(IC$10-NC-PadP$5)") (class "Default")
      (node (ref "IC$10") (pin "P$5") (pinfunction "NC_P$5") (pintype "bidirectional"))
    )
  )
)
